# ser.net
KiCad netlist of a schematic drawn in Altium Designer
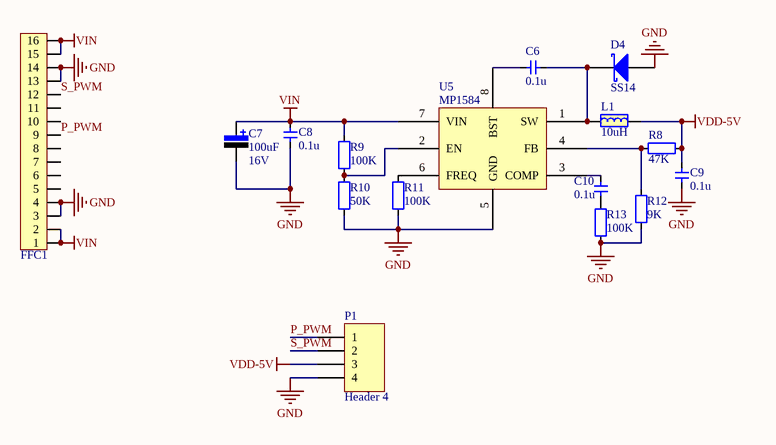
[diagram p0: ser.SchDoc]

(export (version "E")
  (design (tool "Eeschema 10.0.6"))
  (components
    (comp (ref "C6")
      (value "0.1u")
      (footprint "SOL_Init_lib_V4:0603-1")
      (description "Capacitor")
      (fields (field (name "Comment") "电容-0603"))
      (libsource (lib "mLib") (part "电容-0603"))
    )
    (comp (ref "C7")
      (value "100uF")
      (footprint "3528-CAP")
      (description "极性电解电容")
      (fields
        (field (name "VOL") "16V")
        (field (name "Comment") "电容 3528")
        (field (name "PUBLISHER") "Altium Limited")
      )
      (libsource (lib "mLib") (part "电容 3528"))
    )
    (comp (ref "C8")
      (value "0.1u")
      (footprint "SOL_Init_lib_V4:0603-1")
      (description "Capacitor")
      (fields (field (name "Comment") "电容-0603"))
      (libsource (lib "mLib") (part "电容-0603"))
    )
    (comp (ref "C9")
      (value "0.1u")
      (footprint "SOL_Init_lib_V4:0603-1")
      (description "Capacitor")
      (fields (field (name "Comment") "电容-0603"))
      (libsource (lib "mLib") (part "电容-0603"))
    )
    (comp (ref "C10")
      (value "0.1u")
      (footprint "SOL_Init_lib_V4:0603-1")
      (description "Capacitor")
      (fields (field (name "Comment") "电容-0603"))
      (libsource (lib "mLib") (part "电容-0603"))
    )
    (comp (ref "D4") (value "SS14") (footprint "DSO-C2/X2.3") (libsource (lib "saibo_smc") (part "Diode")))
    (comp (ref "FFC1")
      (value "FFC_0.5_16")
      (footprint "X-Bot1:FFC_0.5_16")
      (description "FFC")
      (libsource (lib "Integrated_Library") (part "FFC_0.5_16"))
    )
    (comp (ref "L1")
      (value "10uH")
      (footprint "L-SMD-7")
      (description "磁珠")
      (libsource (lib "mLib") (part "电感-0805"))
    )
    (comp (ref "P1")
      (value "Header 4")
      (footprint "HDR1X4")
      (description "Header, 4-Pin")
      (fields (field (name "PUBLISHER") "Altium Limited"))
      (libsource (lib "saibo_smc") (part "Header 4"))
    )
    (comp (ref "R8")
      (value "47K")
      (footprint "SOL_Init_lib_V4:0603-1")
      (description "Resistor")
      (fields (field (name "Comment") "100K"))
      (libsource (lib "") (part "电阻-0603_1"))
    )
    (comp (ref "R9")
      (value "100K")
      (footprint "SOL_Init_lib_V4:0603-1")
      (description "Resistor")
      (libsource (lib "mLib") (part "电阻-0603"))
    )
    (comp (ref "R10")
      (value "50K")
      (footprint "SOL_Init_lib_V4:0603-1")
      (description "Resistor")
      (fields (field (name "Comment") "100K"))
      (libsource (lib "mLib") (part "电阻-0603"))
    )
    (comp (ref "R11")
      (value "100K")
      (footprint "SOL_Init_lib_V4:0603-1")
      (description "Resistor")
      (libsource (lib "mLib") (part "电阻-0603"))
    )
    (comp (ref "R12")
      (value "9K")
      (footprint "SOL_Init_lib_V4:0603-1")
      (description "Resistor")
      (fields (field (name "Comment") "100K"))
      (libsource (lib "mLib") (part "电阻-0603"))
    )
    (comp (ref "R13")
      (value "100K")
      (footprint "SOL_Init_lib_V4:0603-1")
      (description "Resistor")
      (libsource (lib "mLib") (part "电阻-0603"))
    )
    (comp (ref "U5")
      (value "MP1584")
      (footprint "SO-8")
      (description "电源芯片")
      (libsource (lib "mLib") (part "MP1584"))
    )
  )
  (nets
    (net (code "1") (name "/P_PWM") (class "Default")
      (node (ref "FFC1") (pin "9") (pinfunction "9_9") (pintype "passive"))
      (node (ref "P1") (pin "1") (pinfunction "1_1") (pintype "passive"))
    )
    (net (code "2") (name "/S_PWM") (class "Default")
      (node (ref "FFC1") (pin "12") (pinfunction "12_12") (pintype "passive"))
      (node (ref "P1") (pin "2") (pinfunction "2_2") (pintype "passive"))
    )
    (net (code "3") (name "GND") (class "Default")
      (node (ref "C7") (pin "2") (pinfunction "2_2") (pintype "passive"))
      (node (ref "C8") (pin "1") (pinfunction "1_1") (pintype "passive"))
      (node (ref "C9") (pin "2") (pinfunction "2_2") (pintype "passive"))
      (node (ref "D4") (pin "1") (pinfunction "A_1") (pintype "passive"))
      (node (ref "FFC1") (pin "13") (pinfunction "13_13") (pintype "passive"))
      (node (ref "FFC1") (pin "14") (pinfunction "14_14") (pintype "passive"))
      (node (ref "FFC1") (pin "3") (pinfunction "3_3") (pintype "passive"))
      (node (ref "FFC1") (pin "4") (pinfunction "4_4") (pintype "passive"))
      (node (ref "P1") (pin "4") (pinfunction "4_4") (pintype "passive"))
      (node (ref "R10") (pin "1") (pinfunction "1_1") (pintype "passive"))
      (node (ref "R11") (pin "1") (pinfunction "1_1") (pintype "passive"))
      (node (ref "R12") (pin "1") (pinfunction "1_1") (pintype "passive"))
      (node (ref "R13") (pin "1") (pinfunction "1_1") (pintype "passive"))
      (node (ref "U5") (pin "5") (pinfunction "GND_5") (pintype "passive"))
    )
    (net (code "4") (name "Net-(C10-Pad1)") (class "Default")
      (node (ref "C10") (pin "1") (pinfunction "1_1") (pintype "passive"))
      (node (ref "R13") (pin "2") (pinfunction "2_2") (pintype "passive"))
    )
    (net (code "5") (name "Net-(D4-K)") (class "Default")
      (node (ref "C6") (pin "2") (pinfunction "2_2") (pintype "passive"))
      (node (ref "D4") (pin "2") (pinfunction "K_2") (pintype "passive"))
      (node (ref "L1") (pin "1") (pintype "passive"))
      (node (ref "U5") (pin "1") (pinfunction "SW_1") (pintype "passive"))
    )
    (net (code "6") (name "Net-(U5-BST)") (class "Default")
      (node (ref "C6") (pin "1") (pinfunction "1_1") (pintype "passive"))
      (node (ref "U5") (pin "8") (pinfunction "BST_8") (pintype "passive"))
    )
    (net (code "7") (name "Net-(U5-COMP)") (class "Default")
      (node (ref "C10") (pin "2") (pinfunction "2_2") (pintype "passive"))
      (node (ref "U5") (pin "3") (pinfunction "COMP_3") (pintype "passive"))
    )
    (net (code "8") (name "Net-(U5-EN)") (class "Default")
      (node (ref "R10") (pin "2") (pinfunction "2_2") (pintype "passive"))
      (node (ref "R9") (pin "1") (pinfunction "1_1") (pintype "passive"))
      (node (ref "U5") (pin "2") (pinfunction "EN_2") (pintype "passive"))
    )
    (net (code "9") (name "Net-(U5-FB)") (class "Default")
      (node (ref "R12") (pin "2") (pinfunction "2_2") (pintype "passive"))
      (node (ref "R8") (pin "2") (pinfunction "2_2") (pintype "passive"))
      (node (ref "U5") (pin "4") (pinfunction "FB_4") (pintype "passive"))
    )
    (net (code "10") (name "Net-(U5-FREQ)") (class "Default")
      (node (ref "R11") (pin "2") (pinfunction "2_2") (pintype "passive"))
      (node (ref "U5") (pin "6") (pinfunction "FREQ_6") (pintype "passive"))
    )
    (net (code "11") (name "VDD-5V") (class "Default")
      (node (ref "C9") (pin "1") (pinfunction "1_1") (pintype "passive"))
      (node (ref "L1") (pin "2") (pinfunction "2_2") (pintype "passive"))
      (node (ref "P1") (pin "3") (pinfunction "3_3") (pintype "passive"))
      (node (ref "R8") (pin "1") (pinfunction "1_1") (pintype "passive"))
    )
    (net (code "12") (name "VIN") (class "Default")
      (node (ref "C7") (pin "1") (pinfunction "1_1") (pintype "passive"))
      (node (ref "C8") (pin "2") (pinfunction "2_2") (pintype "passive"))
      (node (ref "FFC1") (pin "1") (pinfunction "1_1") (pintype "passive"))
      (node (ref "FFC1") (pin "15") (pinfunction "15_15") (pintype "passive"))
      (node (ref "FFC1") (pin "16") (pinfunction "16_16") (pintype "passive"))
      (node (ref "FFC1") (pin "2") (pinfunction "2_2") (pintype "passive"))
      (node (ref "R9") (pin "2") (pinfunction "2_2") (pintype "passive"))
      (node (ref "U5") (pin "7") (pinfunction "VIN_7") (pintype "passive"))
    )
    (net (code "13") (name "unconnected-(FFC1-Pad5)") (class "Default")
      (node (ref "FFC1") (pin "5") (pinfunction "5_5") (pintype "passive"))
    )
    (net (code "14") (name "unconnected-(FFC1-Pad6)") (class "Default")
      (node (ref "FFC1") (pin "6") (pinfunction "6_6") (pintype "passive"))
    )
    (net (code "15") (name "unconnected-(FFC1-Pad7)") (class "Default")
      (node (ref "FFC1") (pin "7") (pinfunction "7_7") (pintype "passive"))
    )
    (net (code "16") (name "unconnected-(FFC1-Pad8)") (class "Default")
      (node (ref "FFC1") (pin "8") (pinfunction "8_8") (pintype "passive"))
    )
    (net (code "17") (name "unconnected-(FFC1-Pad10)") (class "Default")
      (node (ref "FFC1") (pin "10") (pinfunction "10_10") (pintype "passive"))
    )
    (net (code "18") (name "unconnected-(FFC1-Pad11)") (class "Default")
      (node (ref "FFC1") (pin "11") (pinfunction "11_11") (pintype "passive"))
    )
  )
)
